# Display-ST0103A2W-WSNLW-F.net
KiCad netlist of a schematic drawn in Altium Designer
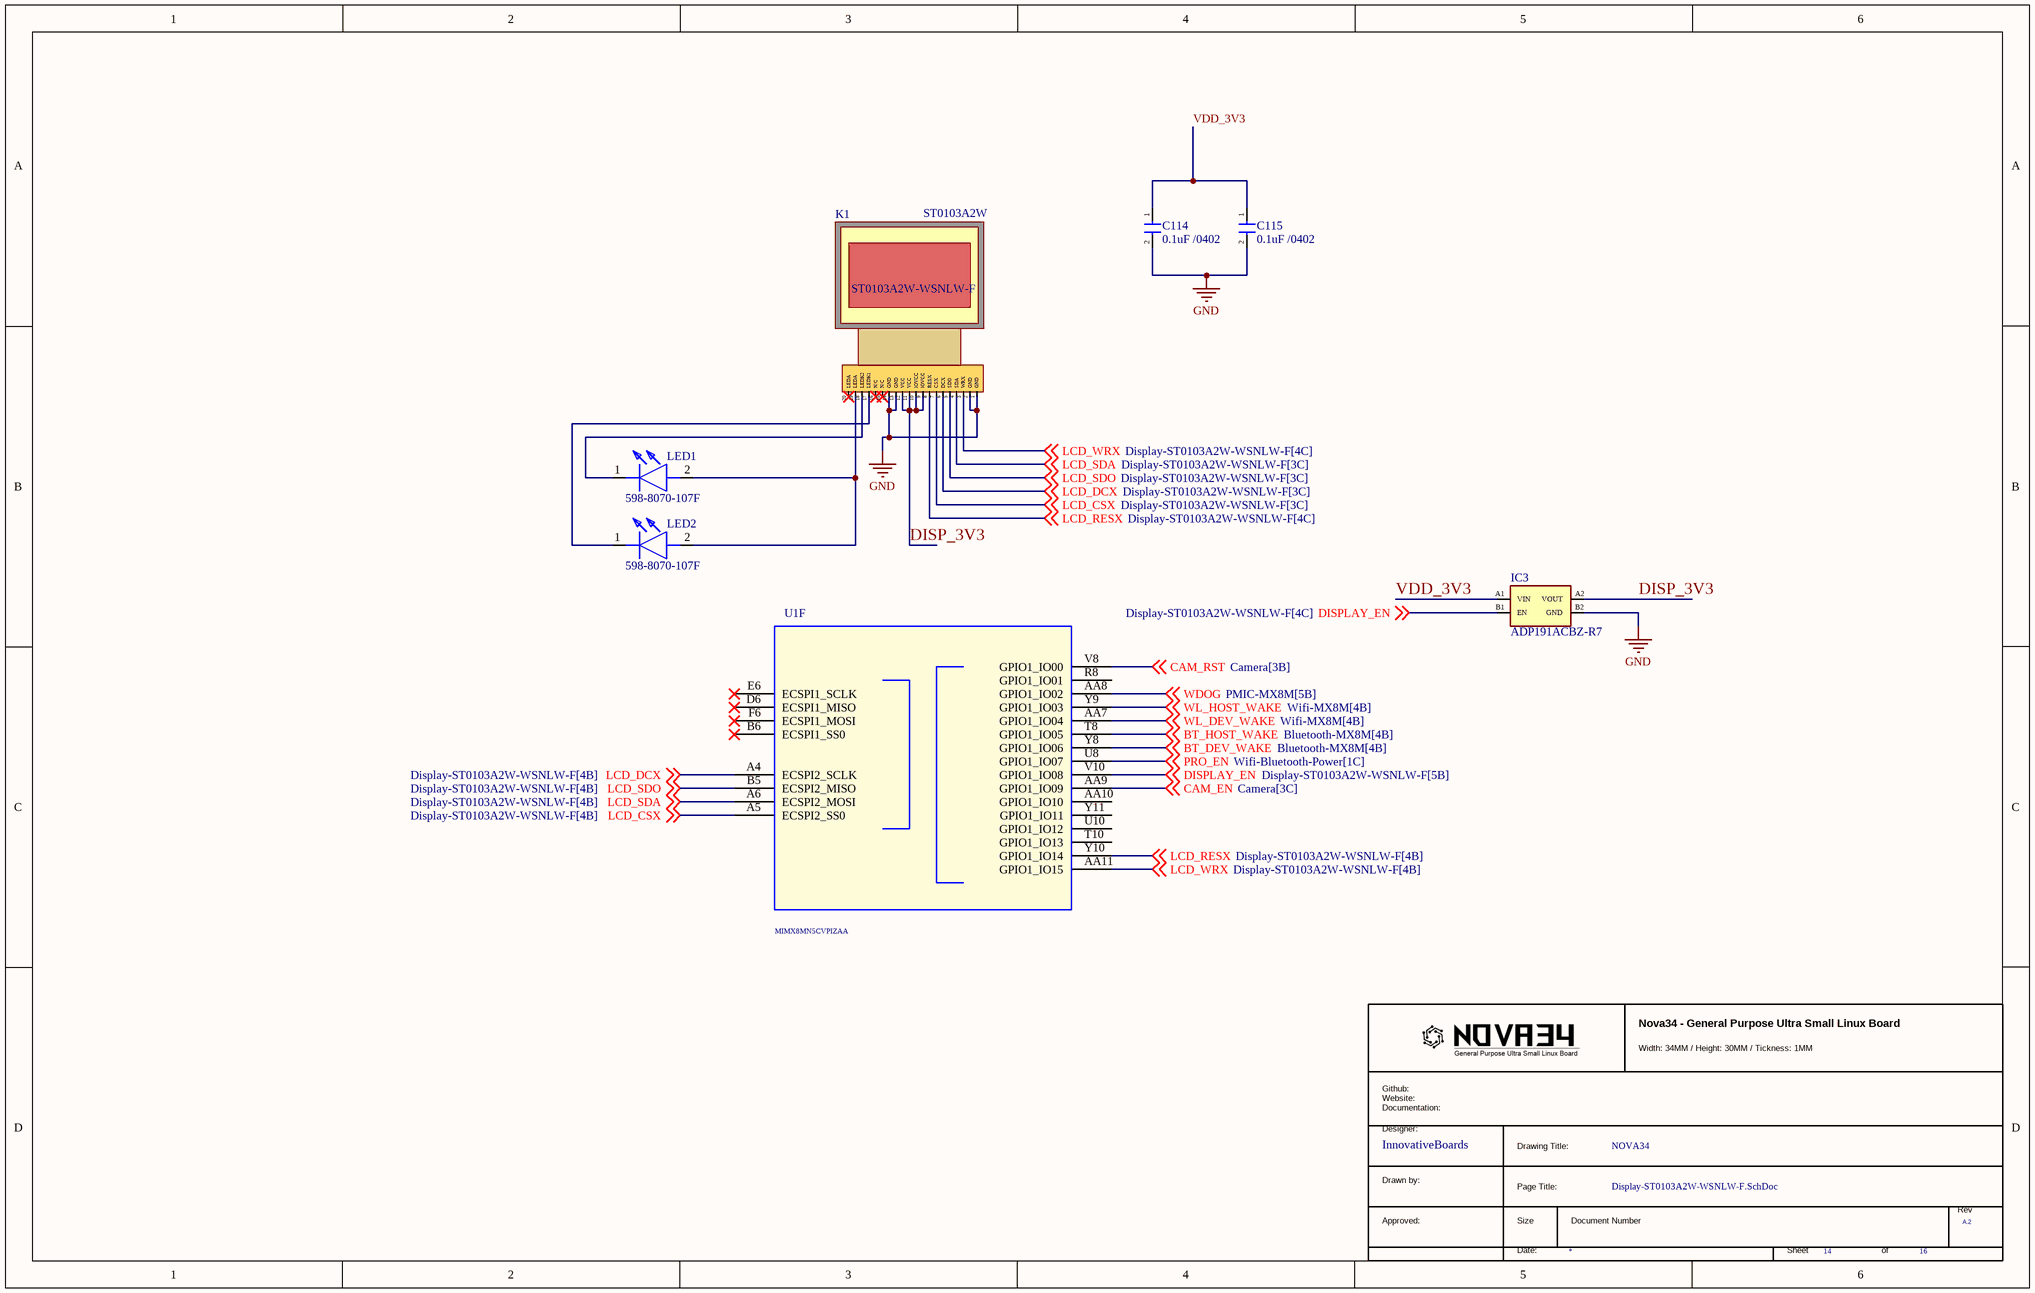
[diagram p0: Display-ST0103A2W-WSNLW-F.SchDoc]

(export (version "E")
  (design (tool "Eeschema 10.0.6"))
  (components
    (comp (ref "*")
      (value "TitleBlock_MCPG")
      (fields (field (name "REVCODE") "A.2"))
      (libsource (lib "Nova_SCHLIB") (part "TitleBlock_MCPG"))
    )
    (comp (ref "C114")
      (value "0.1uF /0402")
      (footprint "CAPC1005X70N")
      (description "Capacitor")
      (fields (field (name "MANUFACTURER_PART_NUMBER") "GRM155R71C104KA88D"))
      (libsource (lib "Nova_SCHLIB") (part "GRM155R71C104KA88D"))
    )
    (comp (ref "C115")
      (value "0.1uF /0402")
      (footprint "CAPC1005X70N")
      (description "Capacitor")
      (fields (field (name "MANUFACTURER_PART_NUMBER") "GRM155R71C104KA88D"))
      (libsource (lib "Nova_SCHLIB") (part "GRM155R71C104KA88D"))
    )
    (comp (ref "IC3")
      (value "ADP191ACBZ-R7")
      (footprint "BGA4C40P2X2_76X76X66")
      (description "Integrated Circuit")
      (fields (field (name "MOUSER PART NUMBER") "584-ADP191ACBZ-R7"))
      (libsource (lib "Nova_SCHLIB") (part "ADP191ACBZ-R7"))
    )
    (comp (ref "K1")
      (value "ST0103A2W")
      (footprint "Display")
      (libsource (lib "Nova_SCHLIB") (part "ST0103A2W"))
    )
    (comp (ref "LED1")
      (value "598-8070-107F")
      (footprint "5988070107F")
      (description "LED")
      (fields (field (name "MOUSER PART NUMBER") "645-598-8070-107F"))
      (libsource (lib "Nova_SCHLIB") (part "598-8070-107F"))
    )
    (comp (ref "LED2")
      (value "598-8070-107F")
      (footprint "5988070107F")
      (description "LED")
      (fields (field (name "MOUSER PART NUMBER") "645-598-8070-107F"))
      (libsource (lib "Nova_SCHLIB") (part "598-8070-107F"))
    )
    (comp (ref "U1")
      (value "MIMX8MN5CVPIZAA")
      (footprint "BGA306C50P21X21_1100X1100X101")
      (description "IC CPU QUAD CORTEX A53+M7 1.4GHZ -- BGA306")
      (libsource (lib "Nova_SCHLIB") (part "MIMX8MN"))
    )
  )
  (nets
    (net (code "1") (name "/DISP_3V3") (class "Default")
      (node (ref "IC3") (pin "A2") (pinfunction "VOUT_A2") (pintype "passive"))
      (node (ref "K1") (pin "10") (pinfunction "lOVCC_10") (pintype "power_in"))
      (node (ref "K1") (pin "11") (pinfunction "VCC_11") (pintype "power_in"))
      (node (ref "K1") (pin "12") (pinfunction "VCC_12") (pintype "power_in"))
      (node (ref "K1") (pin "9") (pinfunction "lOVCC_9") (pintype "power_in"))
    )
    (net (code "2") (name "/VDD_3V3") (class "Default")
      (node (ref "C114") (pin "1") (pinfunction "1_1") (pintype "passive"))
      (node (ref "C115") (pin "1") (pinfunction "1_1") (pintype "passive"))
      (node (ref "IC3") (pin "A1") (pinfunction "VIN_A1") (pintype "passive"))
    )
    (net (code "3") (name "BT_DEV_WAKE") (class "Default")
      (node (ref "U1") (pin "Y8") (pinfunction "GPIO1_IO06_Y8") (pintype "passive"))
    )
    (net (code "4") (name "BT_HOST_WAKE") (class "Default")
      (node (ref "U1") (pin "T8") (pinfunction "GPIO1_IO05_T8") (pintype "passive"))
    )
    (net (code "5") (name "CAM_EN") (class "Default")
      (node (ref "U1") (pin "AA9") (pinfunction "GPIO1_IO09_AA9") (pintype "passive"))
    )
    (net (code "6") (name "CAM_RST") (class "Default")
      (node (ref "U1") (pin "V8") (pinfunction "GPIO1_IO00_V8") (pintype "passive"))
    )
    (net (code "7") (name "DISPLAY_EN") (class "Default")
      (node (ref "IC3") (pin "B1") (pinfunction "EN_B1") (pintype "passive"))
      (node (ref "U1") (pin "V10") (pinfunction "GPIO1_IO08_V10") (pintype "passive"))
    )
    (net (code "8") (name "GND") (class "Default")
      (node (ref "C114") (pin "2") (pinfunction "2_2") (pintype "passive"))
      (node (ref "C115") (pin "2") (pinfunction "2_2") (pintype "passive"))
      (node (ref "IC3") (pin "B2") (pinfunction "GND_B2") (pintype "passive"))
      (node (ref "K1") (pin "1") (pinfunction "GND_1") (pintype "power_in"))
      (node (ref "K1") (pin "13") (pinfunction "GND_13") (pintype "power_in"))
      (node (ref "K1") (pin "14") (pinfunction "GND_14") (pintype "power_in"))
      (node (ref "K1") (pin "2") (pinfunction "GND_2") (pintype "power_in"))
    )
    (net (code "9") (name "LCD_CSX") (class "Default")
      (node (ref "K1") (pin "7") (pinfunction "CSX_7") (pintype "input"))
      (node (ref "U1") (pin "A5") (pinfunction "ECSPI2_SS0_A5") (pintype "passive"))
    )
    (net (code "10") (name "LCD_DCX") (class "Default")
      (node (ref "K1") (pin "6") (pinfunction "DCX_6") (pintype "input"))
      (node (ref "U1") (pin "A4") (pinfunction "ECSPI2_SCLK_A4") (pintype "passive"))
    )
    (net (code "11") (name "LCD_RESX") (class "Default")
      (node (ref "K1") (pin "8") (pinfunction "RESX_8") (pintype "input"))
      (node (ref "U1") (pin "Y10") (pinfunction "GPIO1_IO14_Y10") (pintype "passive"))
    )
    (net (code "12") (name "LCD_SDA") (class "Default")
      (node (ref "K1") (pin "4") (pinfunction "SDA_4") (pintype "input"))
      (node (ref "U1") (pin "A6") (pinfunction "ECSPI2_MOSI_A6") (pintype "passive"))
    )
    (net (code "13") (name "LCD_SDO") (class "Default")
      (node (ref "K1") (pin "5") (pinfunction "SDO_5") (pintype "input"))
      (node (ref "U1") (pin "B5") (pinfunction "ECSPI2_MISO_B5") (pintype "passive"))
    )
    (net (code "14") (name "LCD_WRX") (class "Default")
      (node (ref "K1") (pin "3") (pinfunction "WRX_3") (pintype "input"))
      (node (ref "U1") (pin "AA11") (pinfunction "GPIO1_IO15_AA11") (pintype "passive"))
    )
    (net (code "15") (name "Net-(K1-LEDK1)") (class "Default")
      (node (ref "K1") (pin "17") (pinfunction "LEDK1_17") (pintype "input"))
      (node (ref "LED2") (pin "1") (pinfunction "K_1") (pintype "passive"))
    )
    (net (code "16") (name "Net-(K1-LEDK2)") (class "Default")
      (node (ref "K1") (pin "18") (pinfunction "LEDK2_18") (pintype "input"))
      (node (ref "LED1") (pin "1") (pinfunction "K_1") (pintype "passive"))
    )
    (net (code "17") (name "Net-(LED1-A)") (class "Default")
      (node (ref "K1") (pin "19") (pinfunction "LEDA_19") (pintype "input"))
      (node (ref "LED1") (pin "2") (pinfunction "A_2") (pintype "passive"))
      (node (ref "LED2") (pin "2") (pinfunction "A_2") (pintype "passive"))
    )
    (net (code "18") (name "PRO_EN") (class "Default")
      (node (ref "U1") (pin "U8") (pinfunction "GPIO1_IO07_U8") (pintype "passive"))
    )
    (net (code "19") (name "WDOG") (class "Default")
      (node (ref "U1") (pin "AA8") (pinfunction "GPIO1_IO02_AA8") (pintype "passive"))
    )
    (net (code "20") (name "WL_DEV_WAKE") (class "Default")
      (node (ref "U1") (pin "AA7") (pinfunction "GPIO1_IO04_AA7") (pintype "passive"))
    )
    (net (code "21") (name "WL_HOST_WAKE") (class "Default")
      (node (ref "U1") (pin "Y9") (pinfunction "GPIO1_IO03_Y9") (pintype "passive"))
    )
    (net (code "22") (name "unconnected-(K1-LEDA-Pad20)") (class "Default")
      (node (ref "K1") (pin "20") (pinfunction "LEDA_20") (pintype "input+no_connect"))
    )
    (net (code "23") (name "unconnected-(K1-N{slash}C-Pad15)") (class "Default")
      (node (ref "K1") (pin "15") (pinfunction "N/C_15") (pintype "passive+no_connect"))
    )
    (net (code "24") (name "unconnected-(K1-N{slash}C-Pad16)") (class "Default")
      (node (ref "K1") (pin "16") (pinfunction "N/C_16") (pintype "passive+no_connect"))
    )
    (net (code "25") (name "unconnected-(U1F-ECSPI1_MISO-PadD6)") (class "Default")
      (node (ref "U1") (pin "D6") (pinfunction "ECSPI1_MISO_D6") (pintype "passive+no_connect"))
    )
    (net (code "26") (name "unconnected-(U1F-ECSPI1_MOSI-PadF6)") (class "Default")
      (node (ref "U1") (pin "F6") (pinfunction "ECSPI1_MOSI_F6") (pintype "passive+no_connect"))
    )
    (net (code "27") (name "unconnected-(U1F-ECSPI1_SCLK-PadE6)") (class "Default")
      (node (ref "U1") (pin "E6") (pinfunction "ECSPI1_SCLK_E6") (pintype "passive+no_connect"))
    )
    (net (code "28") (name "unconnected-(U1F-ECSPI1_SS0-PadB6)") (class "Default")
      (node (ref "U1") (pin "B6") (pinfunction "ECSPI1_SS0_B6") (pintype "passive+no_connect"))
    )
    (net (code "29") (name "unconnected-(U1F-GPIO1_IO01-PadR8)") (class "Default")
      (node (ref "U1") (pin "R8") (pinfunction "GPIO1_IO01_R8") (pintype "passive"))
    )
    (net (code "30") (name "unconnected-(U1F-GPIO1_IO10-PadAA10)") (class "Default")
      (node (ref "U1") (pin "AA10") (pinfunction "GPIO1_IO10_AA10") (pintype "passive"))
    )
    (net (code "31") (name "unconnected-(U1F-GPIO1_IO11-PadY11)") (class "Default")
      (node (ref "U1") (pin "Y11") (pinfunction "GPIO1_IO11_Y11") (pintype "passive"))
    )
    (net (code "32") (name "unconnected-(U1F-GPIO1_IO12-PadU10)") (class "Default")
      (node (ref "U1") (pin "U10") (pinfunction "GPIO1_IO12_U10") (pintype "passive"))
    )
    (net (code "33") (name "unconnected-(U1F-GPIO1_IO13-PadT10)") (class "Default")
      (node (ref "U1") (pin "T10") (pinfunction "GPIO1_IO13_T10") (pintype "passive"))
    )
  )
)
